# 7ch_op_amp_board_v40.net
KiCad netlist of a schematic drawn in EAGLE
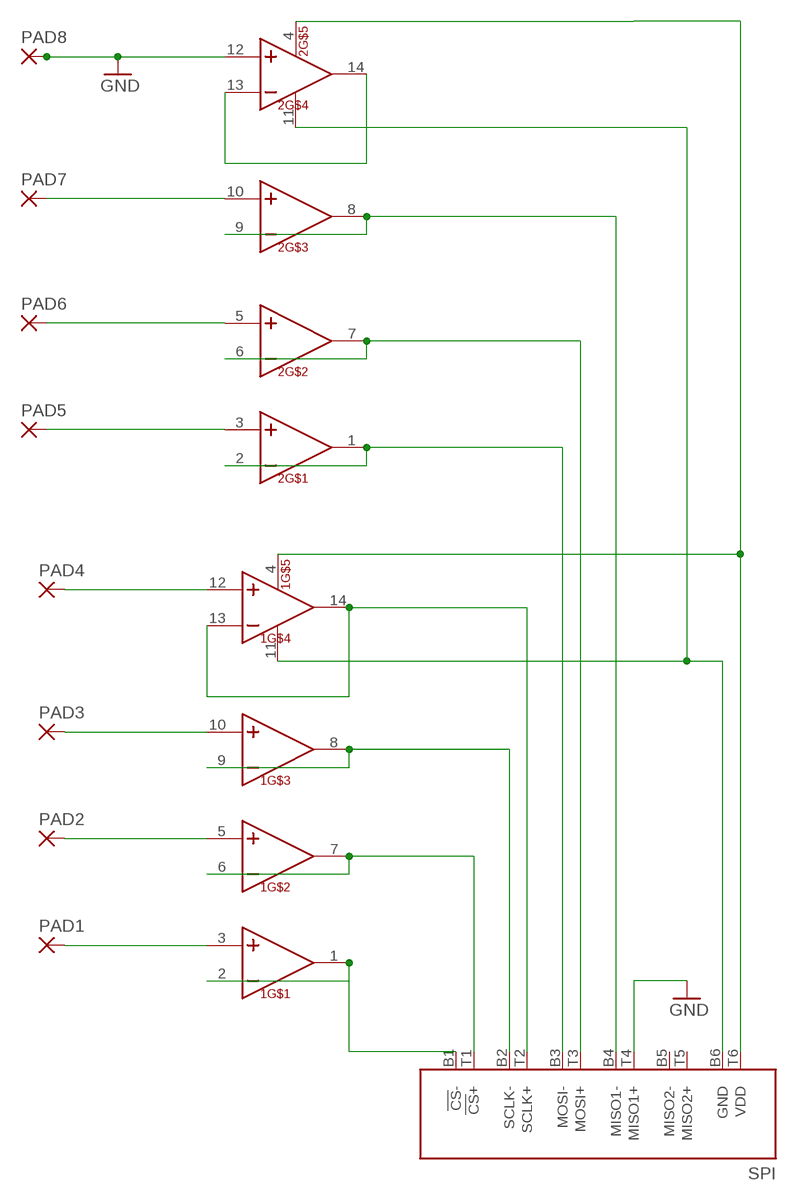
[diagram p0: schematic, sheet 1]

(export (version "E")
  (design (tool "Eeschema 10.0.6"))
  (components
    (comp (ref "1")
      (value "TL074-TSSOP")
      (footprint "eagle-import:TSSOP14")
      (libsource (lib "eagle-import") (part "TL074-TSSOP"))
    )
    (comp (ref "2")
      (value "TL074-TSSOP")
      (footprint "eagle-import:TSSOP14")
      (libsource (lib "eagle-import") (part "TL074-TSSOP"))
    )
    (comp (ref "PAD1")
      (value "1,6/0,8")
      (footprint "eagle-import:1,6_0,8")
      (libsource (lib "eagle-import") (part "1,6/0,8"))
    )
    (comp (ref "PAD2")
      (value "1,6/0,8")
      (footprint "eagle-import:1,6_0,8")
      (libsource (lib "eagle-import") (part "1,6/0,8"))
    )
    (comp (ref "PAD3")
      (value "1,6/0,8")
      (footprint "eagle-import:1,6_0,8")
      (libsource (lib "eagle-import") (part "1,6/0,8"))
    )
    (comp (ref "PAD4")
      (value "1,6/0,8")
      (footprint "eagle-import:1,6_0,8")
      (libsource (lib "eagle-import") (part "1,6/0,8"))
    )
    (comp (ref "PAD5")
      (value "1,6/0,8")
      (footprint "eagle-import:1,6_0,8")
      (libsource (lib "eagle-import") (part "1,6/0,8"))
    )
    (comp (ref "PAD6")
      (value "1,6/0,8")
      (footprint "eagle-import:1,6_0,8")
      (libsource (lib "eagle-import") (part "1,6/0,8"))
    )
    (comp (ref "PAD7")
      (value "1,6/0,8")
      (footprint "eagle-import:1,6_0,8")
      (libsource (lib "eagle-import") (part "1,6/0,8"))
    )
    (comp (ref "PAD8")
      (value "1,6/0,8")
      (footprint "eagle-import:1,6_0,8")
      (libsource (lib "eagle-import") (part "1,6/0,8"))
    )
    (comp (ref "SPI")
      (value "RHD2000-CABLE-AMP-SIDE")
      (footprint "eagle-import:OMNETICS_PZN-12-AA")
      (libsource (lib "eagle-import") (part "RHD2000-CABLE-AMP-SIDE"))
    )
  )
  (nets
    (net (code "1") (name "GND") (class "Default")
      (node (ref "2") (pin "12") (pinfunction "IN+_12") (pintype "input"))
      (node (ref "PAD8") (pin "1") (pinfunction "P_1") (pintype "passive"))
      (node (ref "SPI") (pin "T4") (pinfunction "MISO1+_T4") (pintype "bidirectional"))
    )
    (net (code "2") (name "Net-(1A-IN+)") (class "Default")
      (node (ref "1") (pin "3") (pinfunction "IN+_3") (pintype "input"))
      (node (ref "PAD1") (pin "1") (pinfunction "P_1") (pintype "passive"))
    )
    (net (code "3") (name "Net-(1A-IN-)") (class "Default")
      (node (ref "1") (pin "1") (pinfunction "OUT_1") (pintype "output"))
      (node (ref "1") (pin "2") (pinfunction "IN-_2") (pintype "input"))
      (node (ref "SPI") (pin "B1") (pinfunction "~{CS}-_B1") (pintype "bidirectional"))
    )
    (net (code "4") (name "Net-(1B-IN+)") (class "Default")
      (node (ref "1") (pin "5") (pinfunction "IN+_5") (pintype "input"))
      (node (ref "PAD2") (pin "1") (pinfunction "P_1") (pintype "passive"))
    )
    (net (code "5") (name "Net-(1B-IN-)") (class "Default")
      (node (ref "1") (pin "6") (pinfunction "IN-_6") (pintype "input"))
      (node (ref "1") (pin "7") (pinfunction "OUT_7") (pintype "output"))
      (node (ref "SPI") (pin "T1") (pinfunction "~{CS}+_T1") (pintype "bidirectional"))
    )
    (net (code "6") (name "Net-(1C-IN+)") (class "Default")
      (node (ref "1") (pin "10") (pinfunction "IN+_10") (pintype "input"))
      (node (ref "PAD3") (pin "1") (pinfunction "P_1") (pintype "passive"))
    )
    (net (code "7") (name "Net-(1C-IN-)") (class "Default")
      (node (ref "1") (pin "8") (pinfunction "OUT_8") (pintype "output"))
      (node (ref "1") (pin "9") (pinfunction "IN-_9") (pintype "input"))
      (node (ref "SPI") (pin "B2") (pinfunction "SCLK-_B2") (pintype "bidirectional"))
    )
    (net (code "8") (name "Net-(1D-IN+)") (class "Default")
      (node (ref "1") (pin "12") (pinfunction "IN+_12") (pintype "input"))
      (node (ref "PAD4") (pin "1") (pinfunction "P_1") (pintype "passive"))
    )
    (net (code "9") (name "Net-(1D-IN-)") (class "Default")
      (node (ref "1") (pin "13") (pinfunction "IN-_13") (pintype "input"))
      (node (ref "1") (pin "14") (pinfunction "OUT_14") (pintype "output"))
      (node (ref "SPI") (pin "T2") (pinfunction "SCLK+_T2") (pintype "bidirectional"))
    )
    (net (code "10") (name "Net-(1E-VCC+)") (class "Default")
      (node (ref "1") (pin "4") (pinfunction "VCC+_4") (pintype "power_in"))
      (node (ref "2") (pin "4") (pinfunction "VCC+_4") (pintype "power_in"))
      (node (ref "SPI") (pin "T6") (pinfunction "VDD_T6") (pintype "bidirectional"))
    )
    (net (code "11") (name "Net-(1E-VCC-)") (class "Default")
      (node (ref "1") (pin "11") (pinfunction "VCC-_11") (pintype "power_in"))
      (node (ref "2") (pin "11") (pinfunction "VCC-_11") (pintype "power_in"))
      (node (ref "SPI") (pin "B6") (pinfunction "GND_B6") (pintype "power_in"))
    )
    (net (code "12") (name "Net-(2A-IN+)") (class "Default")
      (node (ref "2") (pin "3") (pinfunction "IN+_3") (pintype "input"))
      (node (ref "PAD5") (pin "1") (pinfunction "P_1") (pintype "passive"))
    )
    (net (code "13") (name "Net-(2A-IN-)") (class "Default")
      (node (ref "2") (pin "1") (pinfunction "OUT_1") (pintype "output"))
      (node (ref "2") (pin "2") (pinfunction "IN-_2") (pintype "input"))
      (node (ref "SPI") (pin "B3") (pinfunction "MOSI-_B3") (pintype "bidirectional"))
    )
    (net (code "14") (name "Net-(2B-IN+)") (class "Default")
      (node (ref "2") (pin "5") (pinfunction "IN+_5") (pintype "input"))
      (node (ref "PAD6") (pin "1") (pinfunction "P_1") (pintype "passive"))
    )
    (net (code "15") (name "Net-(2B-IN-)") (class "Default")
      (node (ref "2") (pin "6") (pinfunction "IN-_6") (pintype "input"))
      (node (ref "2") (pin "7") (pinfunction "OUT_7") (pintype "output"))
      (node (ref "SPI") (pin "T3") (pinfunction "MOSI+_T3") (pintype "bidirectional"))
    )
    (net (code "16") (name "Net-(2C-IN+)") (class "Default")
      (node (ref "2") (pin "10") (pinfunction "IN+_10") (pintype "input"))
      (node (ref "PAD7") (pin "1") (pinfunction "P_1") (pintype "passive"))
    )
    (net (code "17") (name "Net-(2C-IN-)") (class "Default")
      (node (ref "2") (pin "8") (pinfunction "OUT_8") (pintype "output"))
      (node (ref "2") (pin "9") (pinfunction "IN-_9") (pintype "input"))
      (node (ref "SPI") (pin "B4") (pinfunction "MISO1-_B4") (pintype "bidirectional"))
    )
    (net (code "18") (name "Net-(2D-IN-)") (class "Default")
      (node (ref "2") (pin "13") (pinfunction "IN-_13") (pintype "input"))
      (node (ref "2") (pin "14") (pinfunction "OUT_14") (pintype "output"))
    )
    (net (code "19") (name "unconnected-(SPI-MISO2+-PadT5)") (class "Default")
      (node (ref "SPI") (pin "T5") (pinfunction "MISO2+_T5") (pintype "bidirectional"))
    )
    (net (code "20") (name "unconnected-(SPI-MISO2--PadB5)") (class "Default")
      (node (ref "SPI") (pin "B5") (pinfunction "MISO2-_B5") (pintype "bidirectional"))
    )
  )
)
